# EEU.net
KiCad netlist of a schematic drawn in Altium Designer
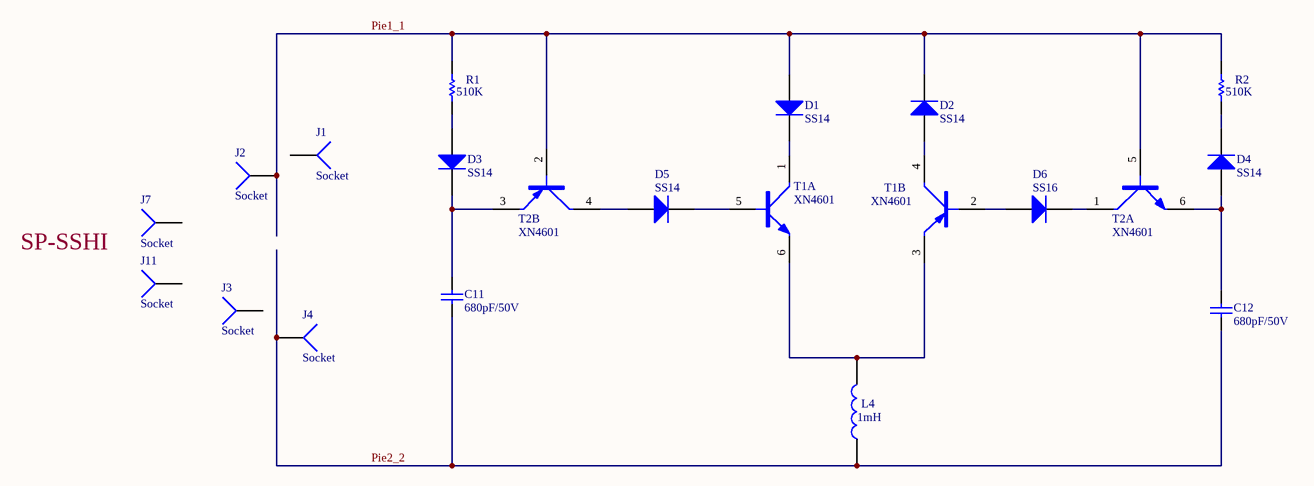
[diagram p0: EEU.SchDoc]

(export (version "E")
  (design (tool "Eeschema 10.0.6"))
  (components
    (comp (ref "C11")
      (value "680pF/50V")
      (footprint "0603C")
      (description "贴片电容")
      (libsource (lib "Harry_PCBLib") (part "Cap"))
    )
    (comp (ref "C12")
      (value "680pF/50V")
      (footprint "0603C")
      (description "贴片电容")
      (libsource (lib "Harry_PCBLib") (part "Cap"))
    )
    (comp (ref "D1")
      (value "SS14")
      (footprint "SOD323")
      (description "1 Amp General Purpose Rectifier")
      (fields (field (name "PUBLISHER") "Altium Limited"))
      (libsource (lib "Miscellaneous Devices") (part "Diode 1N4004"))
    )
    (comp (ref "D2")
      (value "SS14")
      (footprint "SOD323")
      (description "1 Amp General Purpose Rectifier")
      (fields (field (name "PUBLISHER") "Altium Limited"))
      (libsource (lib "Miscellaneous Devices") (part "Diode 1N4004"))
    )
    (comp (ref "D3")
      (value "SS14")
      (footprint "SOD323")
      (description "1 Amp General Purpose Rectifier")
      (fields (field (name "PUBLISHER") "Altium Limited"))
      (libsource (lib "Miscellaneous Devices") (part "Diode 1N4004"))
    )
    (comp (ref "D4")
      (value "SS14")
      (footprint "SOD323")
      (description "1 Amp General Purpose Rectifier")
      (fields (field (name "PUBLISHER") "Altium Limited"))
      (libsource (lib "Miscellaneous Devices") (part "Diode 1N4004"))
    )
    (comp (ref "D5")
      (value "SS14")
      (footprint "SOD323")
      (description "1 Amp General Purpose Rectifier")
      (fields (field (name "PUBLISHER") "Altium Limited"))
      (libsource (lib "Miscellaneous Devices") (part "Diode 1N4004"))
    )
    (comp (ref "D6")
      (value "SS16")
      (footprint "SOD323")
      (description "1 Amp General Purpose Rectifier")
      (fields (field (name "PUBLISHER") "Altium Limited"))
      (libsource (lib "Miscellaneous Devices") (part "Diode 1N4004"))
    )
    (comp (ref "J1")
      (value "Socket")
      (footprint "PIN1")
      (fields (field (name "PUBLISHER") "Altium Limited"))
      (libsource (lib "Miscellaneous Connectors") (part "Socket"))
    )
    (comp (ref "J2")
      (value "Socket")
      (footprint "PIN1")
      (fields (field (name "PUBLISHER") "Altium Limited"))
      (libsource (lib "Miscellaneous Connectors") (part "Socket"))
    )
    (comp (ref "J3")
      (value "Socket")
      (footprint "PIN1")
      (fields (field (name "PUBLISHER") "Altium Limited"))
      (libsource (lib "Miscellaneous Connectors") (part "Socket"))
    )
    (comp (ref "J4")
      (value "Socket")
      (footprint "PIN1")
      (fields (field (name "PUBLISHER") "Altium Limited"))
      (libsource (lib "Miscellaneous Connectors") (part "Socket"))
    )
    (comp (ref "J7")
      (value "Socket")
      (footprint "PIN1")
      (fields (field (name "PUBLISHER") "Altium Limited"))
      (libsource (lib "Miscellaneous Connectors") (part "Socket"))
    )
    (comp (ref "J11")
      (value "Socket")
      (footprint "PIN1")
      (fields (field (name "PUBLISHER") "Altium Limited"))
      (libsource (lib "Miscellaneous Connectors") (part "Socket"))
    )
    (comp (ref "L4") (value "1mH") (footprint "1812") (libsource (lib "Harry_PCBLib") (part "INDUCTOR")))
    (comp (ref "R1")
      (value "510K")
      (footprint "0603")
      (description "贴片电阻")
      (libsource (lib "Miscellaneous Devices") (part "Res1"))
    )
    (comp (ref "R2")
      (value "510K")
      (footprint "0603")
      (description "贴片电阻")
      (libsource (lib "Miscellaneous Devices") (part "Res1"))
    )
    (comp (ref "T1")
      (value "XN4601")
      (footprint "XN4601")
      (description "Composite Transistors")
      (libsource (lib "Self-power SSHI") (part "XN4601"))
    )
    (comp (ref "T2")
      (value "XN4601")
      (footprint "XN4601")
      (libsource (lib "Self-power SSHI") (part "XN4601"))
    )
  )
  (nets
    (net (code "1") (name "/Pie1_1") (class "Default")
      (node (ref "D1") (pin "1") (pinfunction "A_1") (pintype "passive"))
      (node (ref "D2") (pin "2") (pinfunction "K_2") (pintype "passive"))
      (node (ref "J2") (pin "1") (pinfunction "1_1") (pintype "passive"))
      (node (ref "R1") (pin "2") (pinfunction "2_2") (pintype "passive"))
      (node (ref "R2") (pin "2") (pinfunction "2_2") (pintype "passive"))
      (node (ref "T2") (pin "2") (pinfunction "PNP_B_2") (pintype "passive"))
      (node (ref "T2") (pin "5") (pinfunction "NPN_B_5") (pintype "passive"))
    )
    (net (code "2") (name "/Pie2_2") (class "Default")
      (node (ref "C11") (pin "1") (pinfunction "1_1") (pintype "passive"))
      (node (ref "C12") (pin "1") (pinfunction "1_1") (pintype "passive"))
      (node (ref "J4") (pin "1") (pinfunction "1_1") (pintype "passive"))
      (node (ref "L4") (pin "1") (pinfunction "1_1") (pintype "passive"))
    )
    (net (code "3") (name "Net-(D1-K)") (class "Default")
      (node (ref "D1") (pin "2") (pinfunction "K_2") (pintype "passive"))
      (node (ref "T1") (pin "1") (pinfunction "NPN_C_1") (pintype "passive"))
    )
    (net (code "4") (name "Net-(D2-A)") (class "Default")
      (node (ref "D2") (pin "1") (pinfunction "A_1") (pintype "passive"))
      (node (ref "T1") (pin "4") (pinfunction "PNP_C_4") (pintype "passive"))
    )
    (net (code "5") (name "Net-(D3-A)") (class "Default")
      (node (ref "D3") (pin "1") (pinfunction "A_1") (pintype "passive"))
      (node (ref "R1") (pin "1") (pinfunction "1_1") (pintype "passive"))
    )
    (net (code "6") (name "Net-(D3-K)") (class "Default")
      (node (ref "C11") (pin "2") (pinfunction "2_2") (pintype "passive"))
      (node (ref "D3") (pin "2") (pinfunction "K_2") (pintype "passive"))
      (node (ref "T2") (pin "3") (pinfunction "PNP_E_3") (pintype "passive"))
    )
    (net (code "7") (name "Net-(D4-A)") (class "Default")
      (node (ref "C12") (pin "2") (pinfunction "2_2") (pintype "passive"))
      (node (ref "D4") (pin "1") (pinfunction "A_1") (pintype "passive"))
      (node (ref "T2") (pin "6") (pinfunction "NPN_E_6") (pintype "passive"))
    )
    (net (code "8") (name "Net-(D4-K)") (class "Default")
      (node (ref "D4") (pin "2") (pinfunction "K_2") (pintype "passive"))
      (node (ref "R2") (pin "1") (pinfunction "1_1") (pintype "passive"))
    )
    (net (code "9") (name "Net-(D5-A)") (class "Default")
      (node (ref "D5") (pin "1") (pinfunction "A_1") (pintype "passive"))
      (node (ref "T2") (pin "4") (pinfunction "PNP_C_4") (pintype "passive"))
    )
    (net (code "10") (name "Net-(D5-K)") (class "Default")
      (node (ref "D5") (pin "2") (pinfunction "K_2") (pintype "passive"))
      (node (ref "T1") (pin "5") (pinfunction "NPN_B_5") (pintype "passive"))
    )
    (net (code "11") (name "Net-(D6-A)") (class "Default")
      (node (ref "D6") (pin "1") (pinfunction "A_1") (pintype "passive"))
      (node (ref "T1") (pin "2") (pinfunction "PNP_B_2") (pintype "passive"))
    )
    (net (code "12") (name "Net-(D6-K)") (class "Default")
      (node (ref "D6") (pin "2") (pinfunction "K_2") (pintype "passive"))
      (node (ref "T2") (pin "1") (pinfunction "NPN_C_1") (pintype "passive"))
    )
    (net (code "13") (name "Net-(T1A-NPN_E)") (class "Default")
      (node (ref "L4") (pin "2") (pinfunction "2_2") (pintype "passive"))
      (node (ref "T1") (pin "3") (pinfunction "PNP_E_3") (pintype "passive"))
      (node (ref "T1") (pin "6") (pinfunction "NPN_E_6") (pintype "passive"))
    )
    (net (code "14") (name "unconnected-(J1-Pad1)") (class "Default")
      (node (ref "J1") (pin "1") (pinfunction "1_1") (pintype "passive"))
    )
    (net (code "15") (name "unconnected-(J3-Pad1)") (class "Default")
      (node (ref "J3") (pin "1") (pinfunction "1_1") (pintype "passive"))
    )
    (net (code "16") (name "unconnected-(J7-Pad1)") (class "Default")
      (node (ref "J7") (pin "1") (pinfunction "1_1") (pintype "passive"))
    )
    (net (code "17") (name "unconnected-(J11-Pad1)") (class "Default")
      (node (ref "J11") (pin "1") (pinfunction "1_1") (pintype "passive"))
    )
  )
)
